# Connectors.net
KiCad netlist of a schematic drawn in Altium Designer
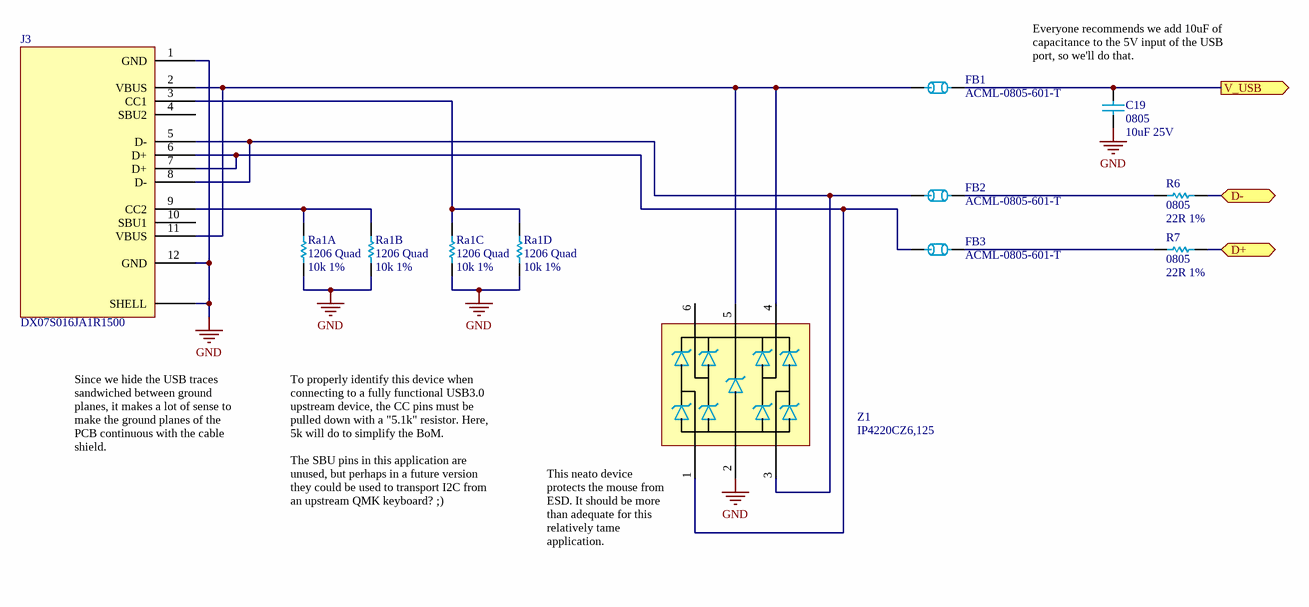
[diagram p0: Connectors.SchDoc]

(export (version "E")
  (design (tool "Eeschema 10.0.6"))
  (components
    (comp (ref "C19")
      (value "0805")
      (footprint "0805")
      (description "0805, X5R or better")
      (fields (field (name "ALTIUM_VALUE") "10uF 25V"))
      (libsource (lib "Chip_Passives") (part "Cap 10uF 25V"))
    )
    (comp (ref "FB1")
      (value "ACML-0805-601-T")
      (footprint "0805")
      (description "FERRITE BEAD 600 OHM 0805 1LN")
      (libsource (lib "Chip_Passives") (part "ACML-0805-601-T"))
    )
    (comp (ref "FB2")
      (value "ACML-0805-601-T")
      (footprint "0805")
      (description "FERRITE BEAD 600 OHM 0805 1LN")
      (libsource (lib "Chip_Passives") (part "ACML-0805-601-T"))
    )
    (comp (ref "FB3")
      (value "ACML-0805-601-T")
      (footprint "0805")
      (description "FERRITE BEAD 600 OHM 0805 1LN")
      (libsource (lib "Chip_Passives") (part "ACML-0805-601-T"))
    )
    (comp (ref "J3")
      (value "DX07S016JA1R1500")
      (footprint "DX07S016JA1R1500")
      (libsource (lib "Connectors") (part "DX07S016JA1R1500"))
    )
    (comp (ref "R6")
      (value "0805")
      (footprint "0805")
      (description "Chip resistor")
      (fields (field (name "ALTIUM_VALUE") "22R 1%"))
      (libsource (lib "Chip_Passives") (part "Res 22R 1% 0805"))
    )
    (comp (ref "R7")
      (value "0805")
      (footprint "0805")
      (description "Chip resistor")
      (fields (field (name "ALTIUM_VALUE") "22R 1%"))
      (libsource (lib "Chip_Passives") (part "Res 22R 1% 0805"))
    )
    (comp (ref "Ra1")
      (value "1206 Quad")
      (footprint "4x 10k 1% - CAC-80P320X160-8M")
      (description "Chip resistor")
      (fields (field (name "ALTIUM_VALUE") "10k 1%"))
      (libsource (lib "Chip_Passives") (part "Quad Res 10k 1% 1206"))
    )
    (comp (ref "Z1")
      (value "IP4220CZ6,125")
      (footprint "PESD3V3S4UD - SOT95P275X110-6N")
      (description "TVS DIODE 5.5V 6TSOP (Low capacitance, USB)")
      (libsource (lib "Diodes") (part "IP4220CZ6,125"))
    )
  )
  (nets
    (net (code "1") (name "/D+") (class "Default")
      (node (ref "R7") (pin "2") (pinfunction "2_2") (pintype "passive"))
    )
    (net (code "2") (name "/D-") (class "Default")
      (node (ref "R6") (pin "2") (pinfunction "2_2") (pintype "passive"))
    )
    (net (code "3") (name "/V_USB") (class "Default")
      (node (ref "C19") (pin "2") (pinfunction "2_2") (pintype "passive"))
      (node (ref "FB1") (pin "2") (pinfunction "2_2") (pintype "passive"))
    )
    (net (code "4") (name "GND") (class "Default")
      (node (ref "C19") (pin "1") (pinfunction "1_1") (pintype "passive"))
      (node (ref "J3") (pin "1") (pinfunction "GND_1") (pintype "passive"))
      (node (ref "J3") (pin "12") (pinfunction "GND_12") (pintype "passive"))
      (node (ref "J3") (pin "SHELL") (pinfunction "SHELL_SHELL") (pintype "passive"))
      (node (ref "Ra1") (pin "1") (pinfunction "1_1") (pintype "passive"))
      (node (ref "Ra1") (pin "2") (pinfunction "2_2") (pintype "passive"))
      (node (ref "Ra1") (pin "3") (pinfunction "3_3") (pintype "passive"))
      (node (ref "Ra1") (pin "4") (pinfunction "4_4") (pintype "passive"))
      (node (ref "Z1") (pin "2") (pinfunction "2_2") (pintype "passive"))
    )
    (net (code "5") (name "Net-(FB1-Pad1)") (class "Default")
      (node (ref "FB1") (pin "1") (pinfunction "1_1") (pintype "passive"))
      (node (ref "J3") (pin "11") (pinfunction "VBUS_11") (pintype "passive"))
      (node (ref "J3") (pin "2") (pinfunction "VBUS_2") (pintype "passive"))
      (node (ref "Z1") (pin "4") (pinfunction "4_4") (pintype "passive"))
      (node (ref "Z1") (pin "5") (pinfunction "5_5") (pintype "passive"))
    )
    (net (code "6") (name "Net-(FB2-Pad1)") (class "Default")
      (node (ref "FB2") (pin "1") (pinfunction "1_1") (pintype "passive"))
      (node (ref "J3") (pin "5") (pinfunction "D-_5") (pintype "passive"))
      (node (ref "J3") (pin "8") (pinfunction "D-_8") (pintype "passive"))
      (node (ref "Z1") (pin "3") (pinfunction "3_3") (pintype "passive"))
    )
    (net (code "7") (name "Net-(FB2-Pad2)") (class "Default")
      (node (ref "FB2") (pin "2") (pinfunction "2_2") (pintype "passive"))
      (node (ref "R6") (pin "1") (pinfunction "1_1") (pintype "passive"))
    )
    (net (code "8") (name "Net-(FB3-Pad1)") (class "Default")
      (node (ref "FB3") (pin "1") (pinfunction "1_1") (pintype "passive"))
      (node (ref "J3") (pin "6") (pinfunction "D+_6") (pintype "passive"))
      (node (ref "J3") (pin "7") (pinfunction "D+_7") (pintype "passive"))
      (node (ref "Z1") (pin "1") (pinfunction "1_1") (pintype "passive"))
    )
    (net (code "9") (name "Net-(FB3-Pad2)") (class "Default")
      (node (ref "FB3") (pin "2") (pinfunction "2_2") (pintype "passive"))
      (node (ref "R7") (pin "1") (pinfunction "1_1") (pintype "passive"))
    )
    (net (code "10") (name "Net-(J3-CC1)") (class "Default")
      (node (ref "J3") (pin "3") (pinfunction "CC1_3") (pintype "passive"))
      (node (ref "Ra1") (pin "5") (pinfunction "5_5") (pintype "passive"))
      (node (ref "Ra1") (pin "6") (pinfunction "6_6") (pintype "passive"))
    )
    (net (code "11") (name "Net-(J3-CC2)") (class "Default")
      (node (ref "J3") (pin "9") (pinfunction "CC2_9") (pintype "passive"))
      (node (ref "Ra1") (pin "7") (pinfunction "7_7") (pintype "passive"))
      (node (ref "Ra1") (pin "8") (pinfunction "8_8") (pintype "passive"))
    )
    (net (code "12") (name "unconnected-(J3-SBU1-Pad10)") (class "Default")
      (node (ref "J3") (pin "10") (pinfunction "SBU1_10") (pintype "passive"))
    )
    (net (code "13") (name "unconnected-(J3-SBU2-Pad4)") (class "Default")
      (node (ref "J3") (pin "4") (pinfunction "SBU2_4") (pintype "passive"))
    )
    (net (code "14") (name "unconnected-(Z1-Pad6)") (class "Default")
      (node (ref "Z1") (pin "6") (pinfunction "6_6") (pintype "passive"))
    )
  )
)
